# GK_Roland_Breakout.net
KiCad netlist of a schematic drawn in EAGLE
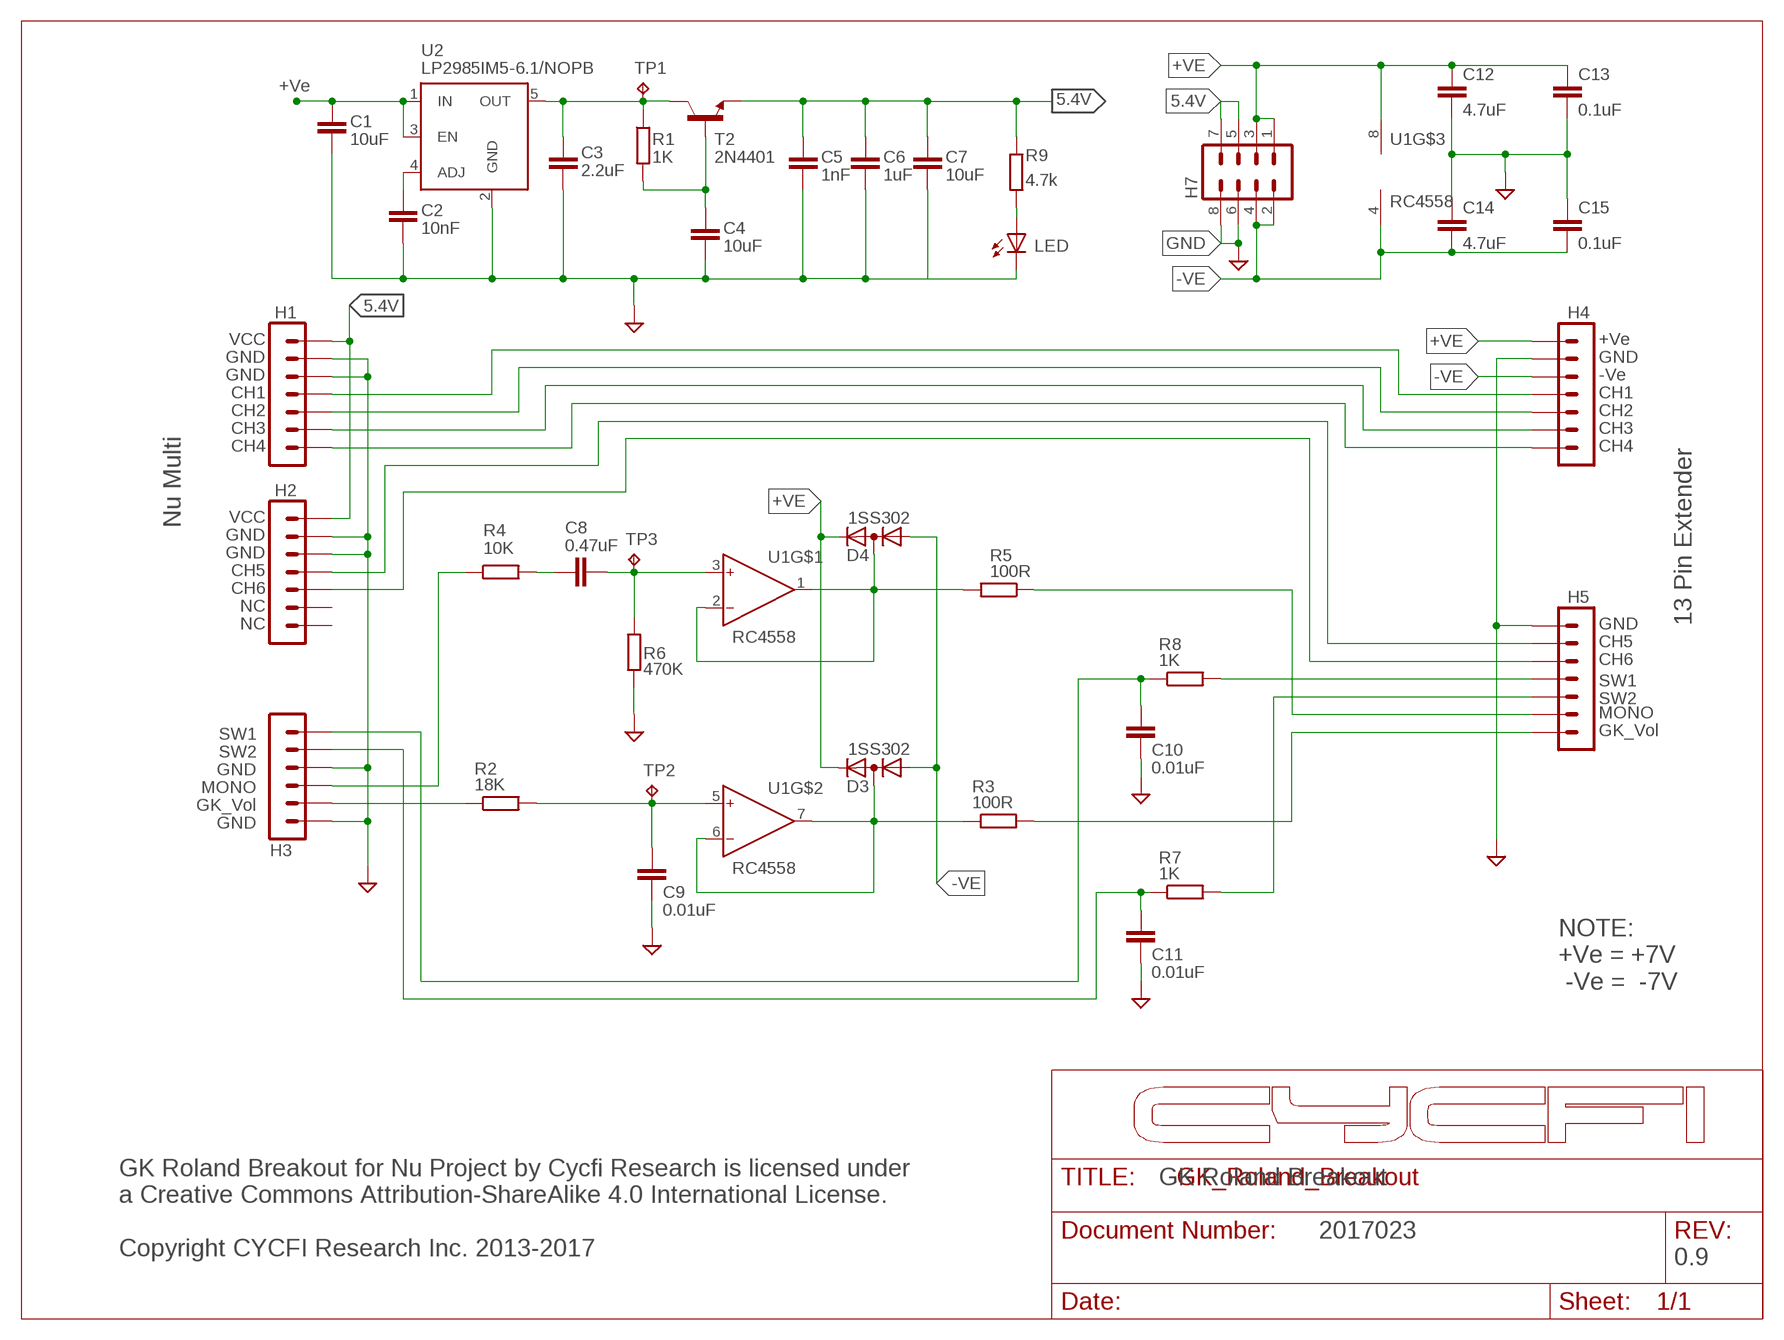
[diagram p0: schematic, sheet 1]

(export (version "E")
  (design (tool "Eeschema 10.0.6"))
  (components
    (comp (ref "C1")
      (value "10uF")
      (footprint "eagle-import:C0805")
      (libsource (lib "eagle-import") (part "C-EUC0805"))
    )
    (comp (ref "C2")
      (value "10nF")
      (footprint "eagle-import:C0805")
      (libsource (lib "eagle-import") (part "C-EUC0805"))
    )
    (comp (ref "C3")
      (value "2.2uF")
      (footprint "eagle-import:C0805")
      (libsource (lib "eagle-import") (part "C-EUC0805"))
    )
    (comp (ref "C4")
      (value "10uF")
      (footprint "eagle-import:C0805")
      (libsource (lib "eagle-import") (part "C-EUC0805"))
    )
    (comp (ref "C5")
      (value "1nF")
      (footprint "eagle-import:C0603")
      (libsource (lib "eagle-import") (part "C-EUC0603"))
    )
    (comp (ref "C6")
      (value "1uF")
      (footprint "eagle-import:C0603")
      (libsource (lib "eagle-import") (part "C-EUC0603"))
    )
    (comp (ref "C7")
      (value "10uF")
      (footprint "eagle-import:C0805")
      (libsource (lib "eagle-import") (part "C-EUC0805"))
    )
    (comp (ref "C8")
      (value "0.47uF")
      (footprint "eagle-import:C0603")
      (libsource (lib "eagle-import") (part "C-EUC0603"))
    )
    (comp (ref "C9")
      (value "0.01uF")
      (footprint "eagle-import:C0805")
      (libsource (lib "eagle-import") (part "C-EUC0805"))
    )
    (comp (ref "C10")
      (value "0.01uF")
      (footprint "eagle-import:C0805")
      (libsource (lib "eagle-import") (part "C-EUC0805"))
    )
    (comp (ref "C11")
      (value "0.01uF")
      (footprint "eagle-import:C0805")
      (libsource (lib "eagle-import") (part "C-EUC0805"))
    )
    (comp (ref "C12")
      (value "4.7uF")
      (footprint "eagle-import:C0805")
      (libsource (lib "eagle-import") (part "C-EUC0805"))
    )
    (comp (ref "C13")
      (value "0.1uF")
      (footprint "eagle-import:C0805")
      (libsource (lib "eagle-import") (part "C-EUC0805"))
    )
    (comp (ref "C14")
      (value "4.7uF")
      (footprint "eagle-import:C0805")
      (libsource (lib "eagle-import") (part "C-EUC0805"))
    )
    (comp (ref "C15")
      (value "0.1uF")
      (footprint "eagle-import:C0805")
      (libsource (lib "eagle-import") (part "C-EUC0805"))
    )
    (comp (ref "D3")
      (value "1SS302")
      (footprint "eagle-import:SC70-3")
      (libsource (lib "eagle-import") (part "1SS302"))
    )
    (comp (ref "D4")
      (value "1SS302")
      (footprint "eagle-import:SC70-3")
      (libsource (lib "eagle-import") (part "1SS302"))
    )
    (comp (ref "H1")
      (value "7P_ZIF_59453-071110EDHLF")
      (footprint "eagle-import:7P_ZIF_59453-071110EDHLF")
      (libsource (lib "eagle-import") (part "7P_ZIF_59453-071110EDHLF"))
    )
    (comp (ref "H2")
      (value "7P_ZIF_59453-071110EDHLF")
      (footprint "eagle-import:7P_ZIF_59453-071110EDHLF")
      (libsource (lib "eagle-import") (part "7P_ZIF_59453-071110EDHLF"))
    )
    (comp (ref "H3")
      (value "6P-2.54-TH")
      (footprint "eagle-import:6P-2.54-TH")
      (libsource (lib "eagle-import") (part "6P-2.54-TH"))
    )
    (comp (ref "H4")
      (value "7P_ZIF_59453-071110EDHLF")
      (footprint "eagle-import:7P_ZIF_59453-071110EDHLF")
      (libsource (lib "eagle-import") (part "7P_ZIF_59453-071110EDHLF"))
    )
    (comp (ref "H5")
      (value "7P_ZIF_59453-071110EDHLF")
      (footprint "eagle-import:7P_ZIF_59453-071110EDHLF")
      (libsource (lib "eagle-import") (part "7P_ZIF_59453-071110EDHLF"))
    )
    (comp (ref "H7")
      (value "MA04-2")
      (footprint "eagle-import:MA04-2")
      (libsource (lib "eagle-import") (part "MA04-2"))
    )
    (comp (ref "LED")
      (value "LED3MM")
      (footprint "eagle-import:LED3MM")
      (libsource (lib "eagle-import") (part "LED3MM"))
    )
    (comp (ref "R1")
      (value "1K")
      (footprint "eagle-import:R0402")
      (libsource (lib "eagle-import") (part "R-EU_R0402"))
    )
    (comp (ref "R2")
      (value "18K")
      (footprint "eagle-import:R0402")
      (libsource (lib "eagle-import") (part "R-EU_R0402"))
    )
    (comp (ref "R3")
      (value "100R")
      (footprint "eagle-import:R0402")
      (libsource (lib "eagle-import") (part "R-EU_R0402"))
    )
    (comp (ref "R4")
      (value "10K")
      (footprint "eagle-import:R0402")
      (libsource (lib "eagle-import") (part "R-EU_R0402"))
    )
    (comp (ref "R5")
      (value "100R")
      (footprint "eagle-import:R0402")
      (libsource (lib "eagle-import") (part "R-EU_R0402"))
    )
    (comp (ref "R6")
      (value "470K")
      (footprint "eagle-import:R0402")
      (libsource (lib "eagle-import") (part "R-EU_R0402"))
    )
    (comp (ref "R7")
      (value "1K")
      (footprint "eagle-import:R0402")
      (libsource (lib "eagle-import") (part "R-EU_R0402"))
    )
    (comp (ref "R8")
      (value "1K")
      (footprint "eagle-import:R0402")
      (libsource (lib "eagle-import") (part "R-EU_R0402"))
    )
    (comp (ref "R9")
      (value "4.7k")
      (footprint "eagle-import:R0402")
      (libsource (lib "eagle-import") (part "R-EU_R0402"))
    )
    (comp (ref "T2")
      (value "2N4401")
      (footprint "eagle-import:SOT23-3")
      (libsource (lib "eagle-import") (part "TRAN-MMBT2222A"))
    )
    (comp (ref "TP1")
      (value "TPB1,27")
      (footprint "eagle-import:B1,27")
      (libsource (lib "eagle-import") (part "TPB1,27"))
    )
    (comp (ref "TP2")
      (value "TPB1,27")
      (footprint "eagle-import:B1,27")
      (libsource (lib "eagle-import") (part "TPB1,27"))
    )
    (comp (ref "TP3")
      (value "TPB1,27")
      (footprint "eagle-import:B1,27")
      (libsource (lib "eagle-import") (part "TPB1,27"))
    )
    (comp (ref "U1")
      (value "RC4558")
      (footprint "eagle-import:SOIC-8")
      (libsource (lib "eagle-import") (part "RC4558"))
    )
    (comp (ref "U2")
      (value "MIC5205-5V")
      (footprint "eagle-import:SOT23-5")
      (fields (field (name "MF") "ALTERA CORPORATION") (field (name "MPN") "MIC5219BM5 TR"))
      (libsource (lib "eagle-import") (part "MIC5219BM5"))
    )
  )
  (nets
    (net (code "1") (name "+VE") (class "Default")
      (node (ref "C1") (pin "1") (pinfunction "1_1") (pintype "passive"))
      (node (ref "C12") (pin "1") (pinfunction "1_1") (pintype "passive"))
      (node (ref "C13") (pin "1") (pinfunction "1_1") (pintype "passive"))
      (node (ref "D3") (pin "2") (pinfunction "K_2") (pintype "passive"))
      (node (ref "D4") (pin "2") (pinfunction "K_2") (pintype "passive"))
      (node (ref "H4") (pin "P$1") (pinfunction "1_P$1") (pintype "passive"))
      (node (ref "H7") (pin "1") (pinfunction "1_1") (pintype "passive"))
      (node (ref "H7") (pin "3") (pinfunction "3_3") (pintype "passive"))
      (node (ref "U1") (pin "8") (pinfunction "V+_8") (pintype "power_in"))
      (node (ref "U2") (pin "1") (pinfunction "IN_1") (pintype "input"))
      (node (ref "U2") (pin "3") (pinfunction "EN_3") (pintype "input"))
    )
    (net (code "2") (name "-VE") (class "Default")
      (node (ref "C14") (pin "2") (pinfunction "2_2") (pintype "passive"))
      (node (ref "C15") (pin "2") (pinfunction "2_2") (pintype "passive"))
      (node (ref "D3") (pin "1") (pinfunction "A_1") (pintype "passive"))
      (node (ref "D4") (pin "1") (pinfunction "A_1") (pintype "passive"))
      (node (ref "H4") (pin "P$3") (pinfunction "3_P$3") (pintype "passive"))
      (node (ref "H7") (pin "2") (pinfunction "2_2") (pintype "passive"))
      (node (ref "H7") (pin "4") (pinfunction "4_4") (pintype "passive"))
      (node (ref "U1") (pin "4") (pinfunction "V-_4") (pintype "power_in"))
    )
    (net (code "3") (name "5.4V") (class "Default")
      (node (ref "C5") (pin "1") (pinfunction "1_1") (pintype "passive"))
      (node (ref "C6") (pin "1") (pinfunction "1_1") (pintype "passive"))
      (node (ref "C7") (pin "1") (pinfunction "1_1") (pintype "passive"))
      (node (ref "H1") (pin "P$1") (pinfunction "1_P$1") (pintype "passive"))
      (node (ref "H2") (pin "P$1") (pinfunction "1_P$1") (pintype "passive"))
      (node (ref "H7") (pin "5") (pinfunction "5_5") (pintype "passive"))
      (node (ref "H7") (pin "7") (pinfunction "7_7") (pintype "passive"))
      (node (ref "R9") (pin "1") (pinfunction "1_1") (pintype "passive"))
      (node (ref "T2") (pin "2") (pinfunction "E_2") (pintype "passive"))
    )
    (net (code "4") (name "GND") (class "Default")
      (node (ref "C1") (pin "2") (pinfunction "2_2") (pintype "passive"))
      (node (ref "C10") (pin "2") (pinfunction "2_2") (pintype "passive"))
      (node (ref "C11") (pin "2") (pinfunction "2_2") (pintype "passive"))
      (node (ref "C12") (pin "2") (pinfunction "2_2") (pintype "passive"))
      (node (ref "C13") (pin "2") (pinfunction "2_2") (pintype "passive"))
      (node (ref "C14") (pin "1") (pinfunction "1_1") (pintype "passive"))
      (node (ref "C15") (pin "1") (pinfunction "1_1") (pintype "passive"))
      (node (ref "C2") (pin "2") (pinfunction "2_2") (pintype "passive"))
      (node (ref "C3") (pin "2") (pinfunction "2_2") (pintype "passive"))
      (node (ref "C4") (pin "2") (pinfunction "2_2") (pintype "passive"))
      (node (ref "C5") (pin "2") (pinfunction "2_2") (pintype "passive"))
      (node (ref "C6") (pin "2") (pinfunction "2_2") (pintype "passive"))
      (node (ref "C7") (pin "2") (pinfunction "2_2") (pintype "passive"))
      (node (ref "C9") (pin "2") (pinfunction "2_2") (pintype "passive"))
      (node (ref "H1") (pin "P$2") (pinfunction "2_P$2") (pintype "passive"))
      (node (ref "H1") (pin "P$3") (pinfunction "3_P$3") (pintype "passive"))
      (node (ref "H2") (pin "P$2") (pinfunction "2_P$2") (pintype "passive"))
      (node (ref "H2") (pin "P$3") (pinfunction "3_P$3") (pintype "passive"))
      (node (ref "H3") (pin "3") (pinfunction "3_3") (pintype "passive"))
      (node (ref "H3") (pin "6") (pinfunction "6_6") (pintype "passive"))
      (node (ref "H4") (pin "P$2") (pinfunction "2_P$2") (pintype "passive"))
      (node (ref "H5") (pin "P$1") (pinfunction "1_P$1") (pintype "passive"))
      (node (ref "H7") (pin "6") (pinfunction "6_6") (pintype "passive"))
      (node (ref "H7") (pin "8") (pinfunction "8_8") (pintype "passive"))
      (node (ref "LED") (pin "K") (pinfunction "C_K") (pintype "passive"))
      (node (ref "R6") (pin "2") (pinfunction "2_2") (pintype "passive"))
      (node (ref "U2") (pin "2") (pinfunction "GND_2") (pintype "power_in"))
    )
    (net (code "5") (name "Net-(C8-Pad2)") (class "Default")
      (node (ref "C8") (pin "2") (pinfunction "2_2") (pintype "passive"))
      (node (ref "R4") (pin "2") (pinfunction "2_2") (pintype "passive"))
    )
    (net (code "6") (name "Net-(C10-Pad1)") (class "Default")
      (node (ref "C10") (pin "1") (pinfunction "1_1") (pintype "passive"))
      (node (ref "H3") (pin "1") (pinfunction "1_1") (pintype "passive"))
      (node (ref "R8") (pin "1") (pinfunction "1_1") (pintype "passive"))
    )
    (net (code "7") (name "Net-(C11-Pad1)") (class "Default")
      (node (ref "C11") (pin "1") (pinfunction "1_1") (pintype "passive"))
      (node (ref "H3") (pin "2") (pinfunction "2_2") (pintype "passive"))
      (node (ref "R7") (pin "1") (pinfunction "1_1") (pintype "passive"))
    )
    (net (code "8") (name "Net-(D3-AK)") (class "Default")
      (node (ref "D3") (pin "3") (pinfunction "AK_3") (pintype "passive"))
      (node (ref "R3") (pin "1") (pinfunction "1_1") (pintype "passive"))
      (node (ref "U1") (pin "6") (pinfunction "IN-_6") (pintype "input"))
      (node (ref "U1") (pin "7") (pinfunction "OUT_7") (pintype "output"))
    )
    (net (code "9") (name "Net-(D4-AK)") (class "Default")
      (node (ref "D4") (pin "3") (pinfunction "AK_3") (pintype "passive"))
      (node (ref "R5") (pin "2") (pinfunction "2_2") (pintype "passive"))
      (node (ref "U1") (pin "1") (pinfunction "OUT_1") (pintype "output"))
      (node (ref "U1") (pin "2") (pinfunction "IN-_2") (pintype "input"))
    )
    (net (code "10") (name "Net-(H1-4)") (class "Default")
      (node (ref "H1") (pin "P$4") (pinfunction "4_P$4") (pintype "passive"))
      (node (ref "H4") (pin "P$4") (pinfunction "4_P$4") (pintype "passive"))
    )
    (net (code "11") (name "Net-(H1-5)") (class "Default")
      (node (ref "H1") (pin "P$5") (pinfunction "5_P$5") (pintype "passive"))
      (node (ref "H4") (pin "P$5") (pinfunction "5_P$5") (pintype "passive"))
    )
    (net (code "12") (name "Net-(H1-6)") (class "Default")
      (node (ref "H1") (pin "P$6") (pinfunction "6_P$6") (pintype "passive"))
      (node (ref "H4") (pin "P$6") (pinfunction "6_P$6") (pintype "passive"))
    )
    (net (code "13") (name "Net-(H1-7)") (class "Default")
      (node (ref "H1") (pin "P$7") (pinfunction "7_P$7") (pintype "passive"))
      (node (ref "H4") (pin "P$7") (pinfunction "7_P$7") (pintype "passive"))
    )
    (net (code "14") (name "Net-(H2-4)") (class "Default")
      (node (ref "H2") (pin "P$4") (pinfunction "4_P$4") (pintype "passive"))
      (node (ref "H5") (pin "P$2") (pinfunction "2_P$2") (pintype "passive"))
    )
    (net (code "15") (name "Net-(H2-5)") (class "Default")
      (node (ref "H2") (pin "P$5") (pinfunction "5_P$5") (pintype "passive"))
      (node (ref "H5") (pin "P$3") (pinfunction "3_P$3") (pintype "passive"))
    )
    (net (code "16") (name "Net-(H3-Pad4)") (class "Default")
      (node (ref "H3") (pin "4") (pinfunction "4_4") (pintype "passive"))
      (node (ref "R4") (pin "1") (pinfunction "1_1") (pintype "passive"))
    )
    (net (code "17") (name "Net-(H3-Pad5)") (class "Default")
      (node (ref "H3") (pin "5") (pinfunction "5_5") (pintype "passive"))
      (node (ref "R2") (pin "1") (pinfunction "1_1") (pintype "passive"))
    )
    (net (code "18") (name "Net-(H5-4)") (class "Default")
      (node (ref "H5") (pin "P$4") (pinfunction "4_P$4") (pintype "passive"))
      (node (ref "R8") (pin "2") (pinfunction "2_2") (pintype "passive"))
    )
    (net (code "19") (name "Net-(H5-5)") (class "Default")
      (node (ref "H5") (pin "P$5") (pinfunction "5_P$5") (pintype "passive"))
      (node (ref "R7") (pin "2") (pinfunction "2_2") (pintype "passive"))
    )
    (net (code "20") (name "Net-(H5-6)") (class "Default")
      (node (ref "H5") (pin "P$6") (pinfunction "6_P$6") (pintype "passive"))
      (node (ref "R5") (pin "1") (pinfunction "1_1") (pintype "passive"))
    )
    (net (code "21") (name "Net-(H5-7)") (class "Default")
      (node (ref "H5") (pin "P$7") (pinfunction "7_P$7") (pintype "passive"))
      (node (ref "R3") (pin "2") (pinfunction "2_2") (pintype "passive"))
    )
    (net (code "22") (name "Net-(LED-PadA)") (class "Default")
      (node (ref "LED") (pin "A") (pinfunction "A_A") (pintype "passive"))
      (node (ref "R9") (pin "2") (pinfunction "2_2") (pintype "passive"))
    )
    (net (code "23") (name "Net-(T2-B)") (class "Default")
      (node (ref "C4") (pin "1") (pinfunction "1_1") (pintype "passive"))
      (node (ref "R1") (pin "2") (pinfunction "2_2") (pintype "passive"))
      (node (ref "T2") (pin "1") (pinfunction "B_1") (pintype "passive"))
    )
    (net (code "24") (name "Net-(T2-C)") (class "Default")
      (node (ref "C3") (pin "1") (pinfunction "1_1") (pintype "passive"))
      (node (ref "R1") (pin "1") (pinfunction "1_1") (pintype "passive"))
      (node (ref "T2") (pin "3") (pinfunction "C_3") (pintype "passive"))
      (node (ref "TP1") (pin "TP") (pinfunction "TP_TP") (pintype "input"))
      (node (ref "U2") (pin "5") (pinfunction "OUT_5") (pintype "output"))
    )
    (net (code "25") (name "Net-(U1A-IN+)") (class "Default")
      (node (ref "C8") (pin "1") (pinfunction "1_1") (pintype "passive"))
      (node (ref "R6") (pin "1") (pinfunction "1_1") (pintype "passive"))
      (node (ref "TP3") (pin "TP") (pinfunction "TP_TP") (pintype "input"))
      (node (ref "U1") (pin "3") (pinfunction "IN+_3") (pintype "input"))
    )
    (net (code "26") (name "Net-(U1B-IN+)") (class "Default")
      (node (ref "C9") (pin "1") (pinfunction "1_1") (pintype "passive"))
      (node (ref "R2") (pin "2") (pinfunction "2_2") (pintype "passive"))
      (node (ref "TP2") (pin "TP") (pinfunction "TP_TP") (pintype "input"))
      (node (ref "U1") (pin "5") (pinfunction "IN+_5") (pintype "input"))
    )
    (net (code "27") (name "Net-(U2-ADJ)") (class "Default")
      (node (ref "C2") (pin "1") (pinfunction "1_1") (pintype "passive"))
      (node (ref "U2") (pin "4") (pinfunction "ADJ_4") (pintype "passive"))
    )
    (net (code "28") (name "unconnected-(H2-6-PadP$6)") (class "Default")
      (node (ref "H2") (pin "P$6") (pinfunction "6_P$6") (pintype "passive"))
    )
    (net (code "29") (name "unconnected-(H2-7-PadP$7)") (class "Default")
      (node (ref "H2") (pin "P$7") (pinfunction "7_P$7") (pintype "passive"))
    )
  )
)
